# esp32_gps_pcb.net
KiCad netlist of a schematic drawn in EAGLE
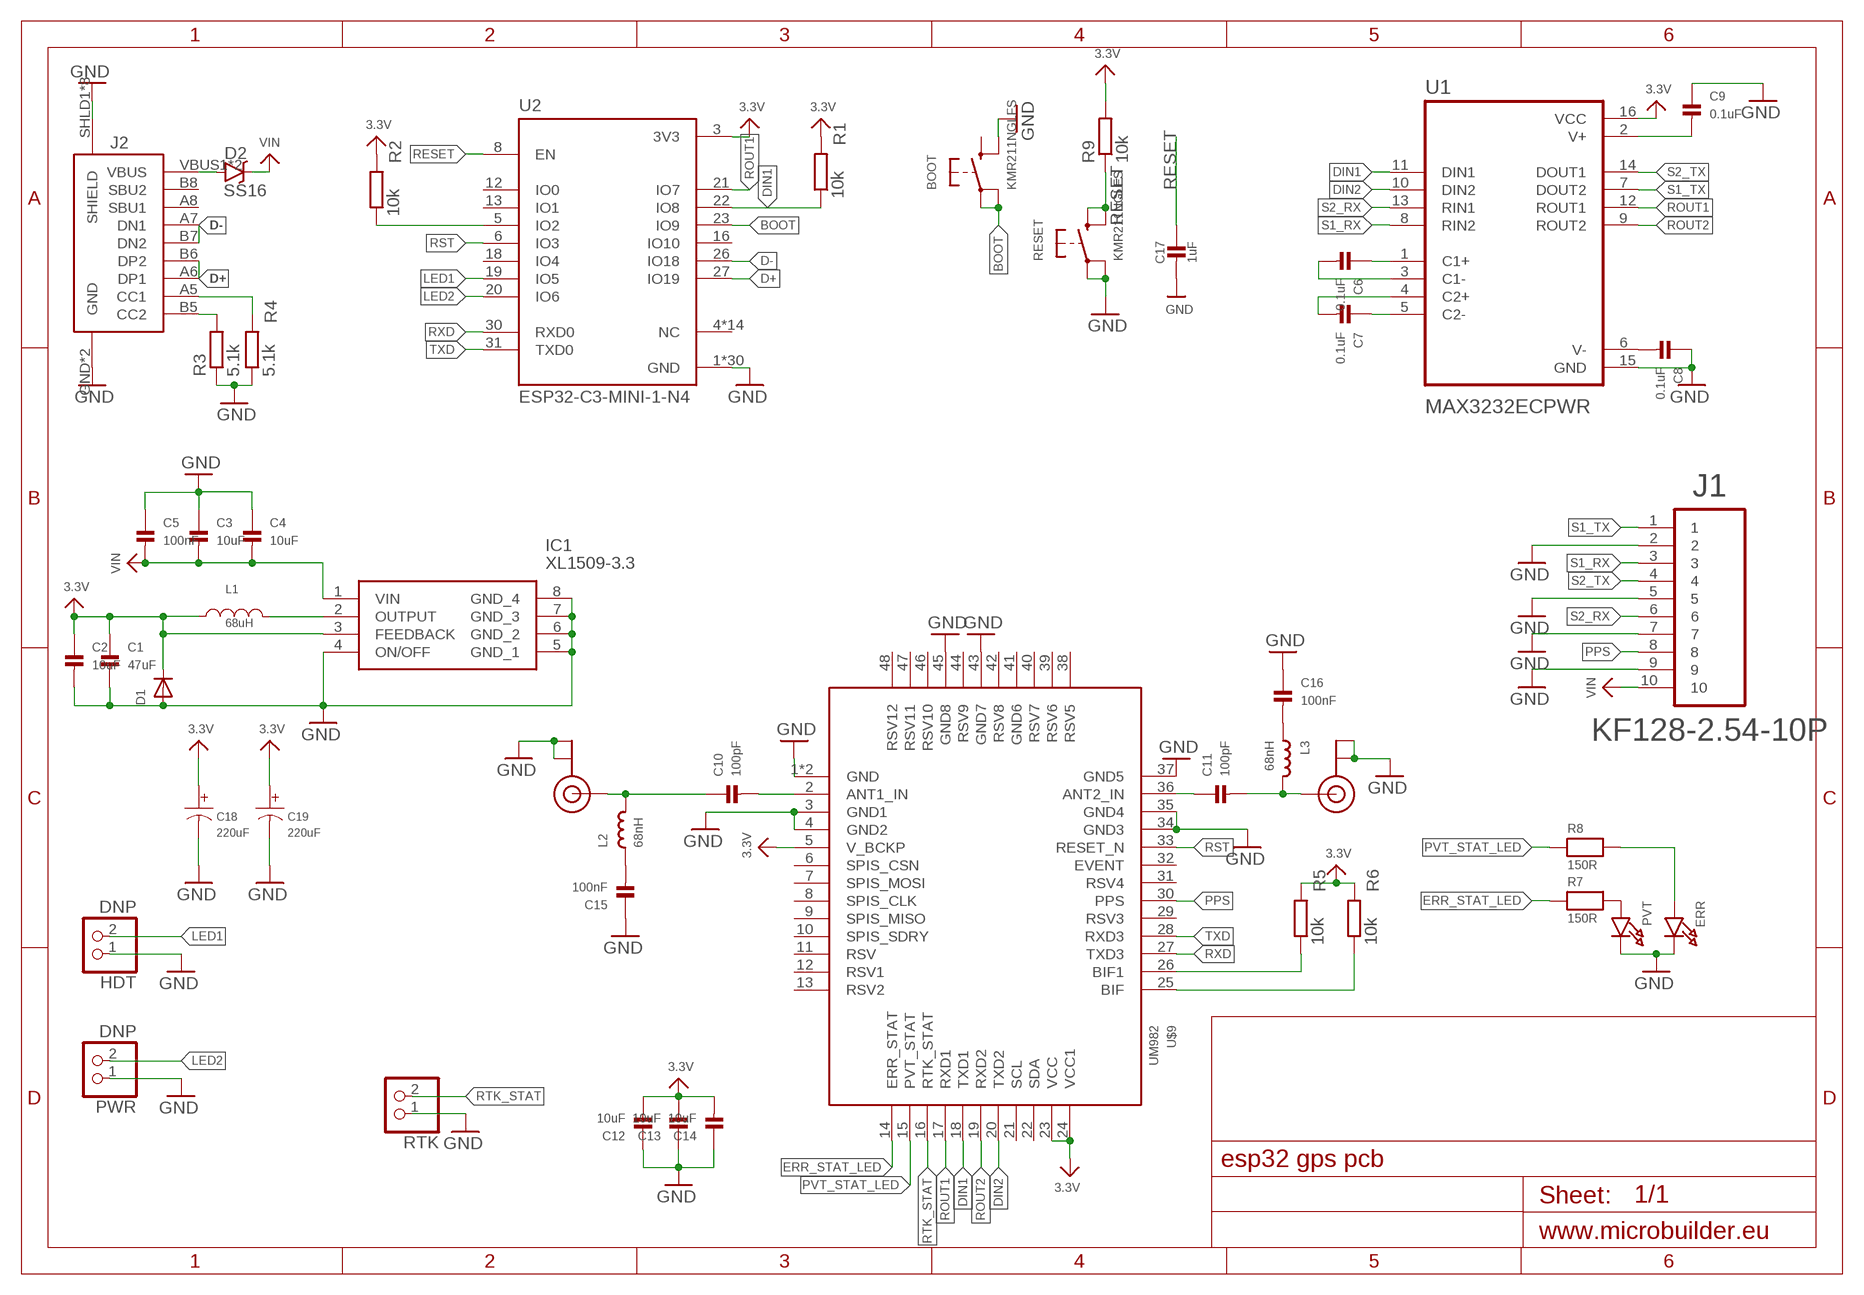
[diagram p0: schematic, sheet 1]

(export (version "E")
  (design (tool "Eeschema 10.0.6"))
  (components
    (comp (ref "BOOT")
      (value "KMR211NGLFS")
      (footprint "eagle-import:BTN_KMR2_4.6X2.8")
      (libsource (lib "eagle-import") (part "SWITCH_TACT_SMT4.6X2.8"))
    )
    (comp (ref "C1")
      (value "47uF")
      (footprint "eagle-import:_0805")
      (libsource (lib "eagle-import") (part "CAP_CERAMIC_0805"))
    )
    (comp (ref "C2")
      (value "10uF")
      (footprint "eagle-import:_0603")
      (libsource (lib "eagle-import") (part "CAP_CERAMIC_0603"))
    )
    (comp (ref "C3")
      (value "10uF")
      (footprint "eagle-import:_0603")
      (libsource (lib "eagle-import") (part "CAP_CERAMIC_0603"))
    )
    (comp (ref "C4")
      (value "10uF")
      (footprint "eagle-import:_0603")
      (libsource (lib "eagle-import") (part "CAP_CERAMIC_0603"))
    )
    (comp (ref "C5")
      (value "100nF")
      (footprint "eagle-import:_0603")
      (libsource (lib "eagle-import") (part "CAP_CERAMIC_0603"))
    )
    (comp (ref "C6")
      (value "0.1uF")
      (footprint "eagle-import:_0603")
      (libsource (lib "eagle-import") (part "CAP_CERAMIC_0603"))
    )
    (comp (ref "C7")
      (value "0.1uF")
      (footprint "eagle-import:_0603")
      (libsource (lib "eagle-import") (part "CAP_CERAMIC_0603"))
    )
    (comp (ref "C8")
      (value "0.1uF")
      (footprint "eagle-import:_0603")
      (libsource (lib "eagle-import") (part "CAP_CERAMIC_0603"))
    )
    (comp (ref "C9")
      (value "0.1uF")
      (footprint "eagle-import:_0603")
      (libsource (lib "eagle-import") (part "CAP_CERAMIC_0603"))
    )
    (comp (ref "C10")
      (value "100pF")
      (footprint "eagle-import:_0603")
      (fields (field (name "SPICEPREFIX") "C"))
      (libsource (lib "eagle-import") (part "CAP_CERAMIC_0603"))
    )
    (comp (ref "C11")
      (value "100pF")
      (footprint "eagle-import:_0603")
      (libsource (lib "eagle-import") (part "CAP_CERAMIC_0603"))
    )
    (comp (ref "C12")
      (value "10uF")
      (footprint "eagle-import:_0603")
      (libsource (lib "eagle-import") (part "CAP_CERAMIC_0603"))
    )
    (comp (ref "C13")
      (value "10uF")
      (footprint "eagle-import:_0603")
      (libsource (lib "eagle-import") (part "CAP_CERAMIC_0603"))
    )
    (comp (ref "C14")
      (value "10uF")
      (footprint "eagle-import:_0603")
      (libsource (lib "eagle-import") (part "CAP_CERAMIC_0603"))
    )
    (comp (ref "C15")
      (value "100nF")
      (footprint "eagle-import:_0603")
      (fields (field (name "SPICEPREFIX") "C"))
      (libsource (lib "eagle-import") (part "CAP_CERAMIC_0603"))
    )
    (comp (ref "C16")
      (value "100nF")
      (footprint "eagle-import:_0603")
      (fields (field (name "SPICEPREFIX") "C"))
      (libsource (lib "eagle-import") (part "CAP_CERAMIC_0603"))
    )
    (comp (ref "C17")
      (value "1uF")
      (footprint "eagle-import:_0603")
      (libsource (lib "eagle-import") (part "CAP_CERAMIC_0603"))
    )
    (comp (ref "C18")
      (value "220uF")
      (footprint "eagle-import:CAP-SMD_BD6.3-L6.6-W6.6-FD")
      (fields
        (field (name "BOM_MANUFACTURER_PART") "RVT1A221M0605")
        (field (name "BOM_SUPPLIER_PART") "C72494")
      )
      (libsource (lib "eagle-import") (part "220UF220UF_CAP-SMD_BD6.3-L6.6-W6.6-FD"))
    )
    (comp (ref "C19")
      (value "220uF")
      (footprint "eagle-import:CAP-SMD_BD6.3-L6.6-W6.6-FD")
      (fields
        (field (name "BOM_MANUFACTURER_PART") "RVT1A221M0605")
        (field (name "BOM_SUPPLIER_PART") "C72494")
      )
      (libsource (lib "eagle-import") (part "220UF220UF_CAP-SMD_BD6.3-L6.6-W6.6-FD"))
    )
    (comp (ref "D1")
      (value "DIODESMA")
      (footprint "eagle-import:SMADIODE")
      (libsource (lib "eagle-import") (part "DIODESMA"))
    )
    (comp (ref "D2")
      (value "SS16")
      (footprint "eagle-import:SMA-DIODE")
      (libsource (lib "eagle-import") (part "DIODE-SCHOTTKY-B340A"))
    )
    (comp (ref "ERR")
      (value "LED0603")
      (footprint "eagle-import:CHIPLED_0603")
      (libsource (lib "eagle-import") (part "LED0603"))
    )
    (comp (ref "HDT")
      (value "DNP")
      (footprint "eagle-import:1X02_ROUND")
      (libsource (lib "eagle-import") (part "HEADER-1X2ROUND"))
    )
    (comp (ref "IC1")
      (value "XL1509-3.3")
      (footprint "eagle-import:SOIC127P600X175-8N")
      (fields (field (name "MANUFACTURER_PART_NUMBER") " XL1509-3.3"))
      (libsource (lib "eagle-import") (part "XL1509-3.3"))
    )
    (comp (ref "J1")
      (value "KF128-2.54-10P")
      (footprint "eagle-import:KF128-2.54-10P")
      (fields
        (field (name "COMMENT") "1-282834-0")
        (field (name "DIGI-KEY_PART_NUMBER") "A98074-ND")
        (field (name "MF") "TE Connectivity")
      )
      (libsource (lib "eagle-import") (part "KF128-2.54-10P"))
    )
    (comp (ref "J2")
      (value "TYP-C16PIN2MD")
      (footprint "eagle-import:USB-C-16P")
      (libsource (lib "eagle-import") (part "TYP-C16PIN2MD"))
    )
    (comp (ref "L1")
      (value "68uH")
      (footprint "eagle-import:IND-SMD_L6.0-W6.0")
      (libsource (lib "eagle-import") (part "PNLS6045_680"))
    )
    (comp (ref "L2")
      (value "68nH")
      (footprint "eagle-import:_0603")
      (libsource (lib "eagle-import") (part "INDUCTOR_0603"))
    )
    (comp (ref "L3")
      (value "68nH")
      (footprint "eagle-import:_0603")
      (libsource (lib "eagle-import") (part "INDUCTOR_0603"))
    )
    (comp (ref "PRI")
      (value "KH-IPEX-K501-29")
      (footprint "eagle-import:U.FL")
      (libsource (lib "eagle-import") (part "U.FL"))
    )
    (comp (ref "PVT")
      (value "LED0603")
      (footprint "eagle-import:CHIPLED_0603")
      (libsource (lib "eagle-import") (part "LED0603"))
    )
    (comp (ref "PWR")
      (value "DNP")
      (footprint "eagle-import:1X02_ROUND")
      (libsource (lib "eagle-import") (part "HEADER-1X2ROUND"))
    )
    (comp (ref "R1")
      (value "10k")
      (footprint "eagle-import:R0402")
      (libsource (lib "eagle-import") (part "R-EU_R0402"))
    )
    (comp (ref "R2")
      (value "10k")
      (footprint "eagle-import:R0402")
      (libsource (lib "eagle-import") (part "R-EU_R0402"))
    )
    (comp (ref "R3")
      (value "5.1k")
      (footprint "eagle-import:R0402")
      (libsource (lib "eagle-import") (part "R-EU_R0402"))
    )
    (comp (ref "R4")
      (value "5.1k")
      (footprint "eagle-import:R0402")
      (libsource (lib "eagle-import") (part "R-EU_R0402"))
    )
    (comp (ref "R5")
      (value "10k")
      (footprint "eagle-import:R0402")
      (libsource (lib "eagle-import") (part "R-EU_R0402"))
    )
    (comp (ref "R6")
      (value "10k")
      (footprint "eagle-import:R0402")
      (libsource (lib "eagle-import") (part "R-EU_R0402"))
    )
    (comp (ref "R7")
      (value "150R")
      (footprint "eagle-import:_0603")
      (libsource (lib "eagle-import") (part "RESISTOR_0603"))
    )
    (comp (ref "R8")
      (value "150R")
      (footprint "eagle-import:_0603")
      (libsource (lib "eagle-import") (part "RESISTOR_0603"))
    )
    (comp (ref "R9")
      (value "10k")
      (footprint "eagle-import:R0603")
      (libsource (lib "eagle-import") (part "R-EU_R0603"))
    )
    (comp (ref "RESET")
      (value "KMR211NGLFS")
      (footprint "eagle-import:BTN_KMR2_4.6X2.8")
      (libsource (lib "eagle-import") (part "SWITCH_TACT_SMT4.6X2.8"))
    )
    (comp (ref "RTK")
      (value "HEADER-1X2ROUND")
      (footprint "eagle-import:1X02_ROUND")
      (libsource (lib "eagle-import") (part "HEADER-1X2ROUND"))
    )
    (comp (ref "SEC")
      (value "KH-IPEX-K501-29")
      (footprint "eagle-import:U.FL")
      (libsource (lib "eagle-import") (part "U.FL"))
    )
    (comp (ref "U$9")
      (value "UM982")
      (footprint "eagle-import:UM982")
      (libsource (lib "eagle-import") (part "UM982"))
    )
    (comp (ref "U1")
      (value "MAX3232ECPWR")
      (footprint "eagle-import:SOP65P640X120-16N")
      (libsource (lib "eagle-import") (part "MAX3232ECPWR"))
    )
    (comp (ref "U2")
      (value "ESP32-C3-MINI-1-N4")
      (footprint "eagle-import:XCVR_ESP32-C3-MINI-1-N4")
      (fields (field (name "MF") "Espressif Systems"))
      (libsource (lib "eagle-import") (part "ESP32-C3-MINI-1-N4"))
    )
  )
  (nets
    (net (code "1") (name "3.3V") (class "Default")
      (node (ref "C1") (pin "1") (pinfunction "P$1_1") (pintype "passive"))
      (node (ref "C12") (pin "2") (pinfunction "P$2_2") (pintype "passive"))
      (node (ref "C13") (pin "2") (pinfunction "P$2_2") (pintype "passive"))
      (node (ref "C14") (pin "2") (pinfunction "P$2_2") (pintype "passive"))
      (node (ref "C18") (pin "1") (pinfunction "1_1") (pintype "passive"))
      (node (ref "C19") (pin "1") (pinfunction "1_1") (pintype "passive"))
      (node (ref "C2") (pin "1") (pinfunction "P$1_1") (pintype "passive"))
      (node (ref "D1") (pin "C") (pinfunction "C_C") (pintype "passive"))
      (node (ref "IC1") (pin "3") (pinfunction "FEEDBACK_3") (pintype "bidirectional"))
      (node (ref "L1") (pin "1") (pinfunction "1_1") (pintype "passive"))
      (node (ref "R1") (pin "2") (pinfunction "2_2") (pintype "passive"))
      (node (ref "R2") (pin "2") (pinfunction "2_2") (pintype "passive"))
      (node (ref "R5") (pin "2") (pinfunction "2_2") (pintype "passive"))
      (node (ref "R6") (pin "2") (pinfunction "2_2") (pintype "passive"))
      (node (ref "R9") (pin "2") (pinfunction "2_2") (pintype "passive"))
      (node (ref "U$9") (pin "23") (pinfunction "VCC_23") (pintype "bidirectional"))
      (node (ref "U$9") (pin "24") (pinfunction "VCC1_24") (pintype "bidirectional"))
      (node (ref "U$9") (pin "5") (pinfunction "V_BCKP_5") (pintype "bidirectional"))
      (node (ref "U1") (pin "16") (pinfunction "VCC_16") (pintype "power_in"))
      (node (ref "U2") (pin "3") (pinfunction "3V3_3") (pintype "power_in"))
    )
    (net (code "2") (name "BOOT") (class "Default")
      (node (ref "BOOT") (pin "A") (pinfunction "P_A") (pintype "passive"))
      (node (ref "BOOT") (pin "A'") (pinfunction "P1_A'") (pintype "passive"))
      (node (ref "U2") (pin "23") (pinfunction "IO9_23") (pintype "bidirectional"))
    )
    (net (code "3") (name "D+") (class "Default")
      (node (ref "J2") (pin "A6") (pinfunction "DP1_A6") (pintype "bidirectional"))
      (node (ref "J2") (pin "B6") (pinfunction "DP2_B6") (pintype "bidirectional"))
      (node (ref "U2") (pin "27") (pinfunction "IO19_27") (pintype "bidirectional"))
    )
    (net (code "4") (name "D-") (class "Default")
      (node (ref "J2") (pin "A7") (pinfunction "DN1_A7") (pintype "bidirectional"))
      (node (ref "J2") (pin "B7") (pinfunction "DN2_B7") (pintype "bidirectional"))
      (node (ref "U2") (pin "26") (pinfunction "IO18_26") (pintype "bidirectional"))
    )
    (net (code "5") (name "DIN1") (class "Default")
      (node (ref "R1") (pin "1") (pinfunction "1_1") (pintype "passive"))
      (node (ref "U$9") (pin "18") (pinfunction "TXD1_18") (pintype "bidirectional"))
      (node (ref "U1") (pin "11") (pinfunction "DIN1_11") (pintype "input"))
      (node (ref "U2") (pin "22") (pinfunction "IO8_22") (pintype "bidirectional"))
    )
    (net (code "6") (name "DIN2") (class "Default")
      (node (ref "U$9") (pin "20") (pinfunction "TXD2_20") (pintype "bidirectional"))
      (node (ref "U1") (pin "10") (pinfunction "DIN2_10") (pintype "input"))
    )
    (net (code "7") (name "ERR_STAT_LED") (class "Default")
      (node (ref "R7") (pin "1") (pinfunction "1_1") (pintype "passive"))
      (node (ref "U$9") (pin "14") (pinfunction "ERR_STAT_14") (pintype "bidirectional"))
    )
    (net (code "8") (name "GND") (class "Default")
      (node (ref "BOOT") (pin "B'") (pinfunction "S1_B'") (pintype "passive"))
      (node (ref "C1") (pin "2") (pinfunction "P$2_2") (pintype "passive"))
      (node (ref "C12") (pin "1") (pinfunction "P$1_1") (pintype "passive"))
      (node (ref "C13") (pin "1") (pinfunction "P$1_1") (pintype "passive"))
      (node (ref "C14") (pin "1") (pinfunction "P$1_1") (pintype "passive"))
      (node (ref "C15") (pin "1") (pinfunction "P$1_1") (pintype "passive"))
      (node (ref "C16") (pin "1") (pinfunction "P$1_1") (pintype "passive"))
      (node (ref "C17") (pin "2") (pinfunction "P$2_2") (pintype "passive"))
      (node (ref "C18") (pin "2") (pinfunction "2_2") (pintype "passive"))
      (node (ref "C19") (pin "2") (pinfunction "2_2") (pintype "passive"))
      (node (ref "C2") (pin "2") (pinfunction "P$2_2") (pintype "passive"))
      (node (ref "C3") (pin "1") (pinfunction "P$1_1") (pintype "passive"))
      (node (ref "C4") (pin "1") (pinfunction "P$1_1") (pintype "passive"))
      (node (ref "C5") (pin "1") (pinfunction "P$1_1") (pintype "passive"))
      (node (ref "C8") (pin "1") (pinfunction "P$1_1") (pintype "passive"))
      (node (ref "C9") (pin "1") (pinfunction "P$1_1") (pintype "passive"))
      (node (ref "D1") (pin "A") (pinfunction "A_A") (pintype "passive"))
      (node (ref "ERR") (pin "C") (pinfunction "C_C") (pintype "passive"))
      (node (ref "HDT") (pin "1") (pinfunction "1_1") (pintype "passive"))
      (node (ref "IC1") (pin "4") (pinfunction "ON/OFF_4") (pintype "bidirectional"))
      (node (ref "IC1") (pin "5") (pinfunction "GND_1_5") (pintype "bidirectional"))
      (node (ref "IC1") (pin "6") (pinfunction "GND_2_6") (pintype "bidirectional"))
      (node (ref "IC1") (pin "7") (pinfunction "GND_3_7") (pintype "bidirectional"))
      (node (ref "IC1") (pin "8") (pinfunction "GND_4_8") (pintype "bidirectional"))
      (node (ref "J1") (pin "2") (pinfunction "2_2") (pintype "passive"))
      (node (ref "J1") (pin "5") (pinfunction "5_5") (pintype "passive"))
      (node (ref "J1") (pin "7") (pinfunction "7_7") (pintype "passive"))
      (node (ref "J1") (pin "9") (pinfunction "9_9") (pintype "passive"))
      (node (ref "J2") (pin "GND") (pinfunction "GND_GND") (pintype "power_in"))
      (node (ref "J2") (pin "GND2") (pinfunction "GND_GND2") (pintype "power_in"))
      (node (ref "J2") (pin "SHLD1") (pinfunction "SHIELD_SHLD1") (pintype "passive"))
      (node (ref "J2") (pin "SHLD2") (pinfunction "SHIELD_SHLD2") (pintype "passive"))
      (node (ref "J2") (pin "SHLD3") (pinfunction "SHIELD_SHLD3") (pintype "passive"))
      (node (ref "J2") (pin "SHLD4") (pinfunction "SHIELD_SHLD4") (pintype "passive"))
      (node (ref "J2") (pin "SHLD5") (pinfunction "SHIELD_SHLD5") (pintype "passive"))
      (node (ref "J2") (pin "SHLD6") (pinfunction "SHIELD_SHLD6") (pintype "passive"))
      (node (ref "J2") (pin "SHLD7") (pinfunction "SHIELD_SHLD7") (pintype "passive"))
      (node (ref "J2") (pin "SHLD8") (pinfunction "SHIELD_SHLD8") (pintype "passive"))
      (node (ref "PRI") (pin "1") (pinfunction "GND_1") (pintype "passive"))
      (node (ref "PRI") (pin "2") (pinfunction "GND_2") (pintype "passive"))
      (node (ref "PVT") (pin "C") (pinfunction "C_C") (pintype "passive"))
      (node (ref "PWR") (pin "1") (pinfunction "1_1") (pintype "passive"))
      (node (ref "R3") (pin "1") (pinfunction "1_1") (pintype "passive"))
      (node (ref "R4") (pin "1") (pinfunction "1_1") (pintype "passive"))
      (node (ref "RESET") (pin "A") (pinfunction "P_A") (pintype "passive"))
      (node (ref "RESET") (pin "A'") (pinfunction "P1_A'") (pintype "passive"))
      (node (ref "RTK") (pin "1") (pinfunction "1_1") (pintype "passive"))
      (node (ref "SEC") (pin "1") (pinfunction "GND_1") (pintype "passive"))
      (node (ref "SEC") (pin "2") (pinfunction "GND_2") (pintype "passive"))
      (node (ref "U$9") (pin "1") (pinfunction "GND_1") (pintype "bidirectional"))
      (node (ref "U$9") (pin "3") (pinfunction "GND1_3") (pintype "bidirectional"))
      (node (ref "U$9") (pin "34") (pinfunction "GND3_34") (pintype "bidirectional"))
      (node (ref "U$9") (pin "35") (pinfunction "GND4_35") (pintype "bidirectional"))
      (node (ref "U$9") (pin "37") (pinfunction "GND5_37") (pintype "bidirectional"))
      (node (ref "U$9") (pin "4") (pinfunction "GND2_4") (pintype "bidirectional"))
      (node (ref "U$9") (pin "43") (pinfunction "GND7_43") (pintype "bidirectional"))
      (node (ref "U$9") (pin "45") (pinfunction "GND8_45") (pintype "bidirectional"))
      (node (ref "U$9") (pin "P$1") (pinfunction "GND_P$1") (pintype "bidirectional"))
      (node (ref "U1") (pin "15") (pinfunction "GND_15") (pintype "power_in"))
      (node (ref "U2") (pin "1") (pinfunction "GND_1") (pintype "power_in"))
      (node (ref "U2") (pin "11") (pinfunction "GND_11") (pintype "power_in"))
      (node (ref "U2") (pin "14") (pinfunction "GND_14") (pintype "power_in"))
      (node (ref "U2") (pin "2") (pinfunction "GND_2") (pintype "power_in"))
      (node (ref "U2") (pin "36") (pinfunction "GND_36") (pintype "power_in"))
      (node (ref "U2") (pin "37") (pinfunction "GND_37") (pintype "power_in"))
      (node (ref "U2") (pin "38") (pinfunction "GND_38") (pintype "power_in"))
      (node (ref "U2") (pin "39") (pinfunction "GND_39") (pintype "power_in"))
      (node (ref "U2") (pin "40") (pinfunction "GND_40") (pintype "power_in"))
      (node (ref "U2") (pin "41") (pinfunction "GND_41") (pintype "power_in"))
      (node (ref "U2") (pin "42") (pinfunction "GND_42") (pintype "power_in"))
      (node (ref "U2") (pin "43") (pinfunction "GND_43") (pintype "power_in"))
      (node (ref "U2") (pin "44") (pinfunction "GND_44") (pintype "power_in"))
      (node (ref "U2") (pin "45") (pinfunction "GND_45") (pintype "power_in"))
      (node (ref "U2") (pin "46") (pinfunction "GND_46") (pintype "power_in"))
      (node (ref "U2") (pin "47") (pinfunction "GND_47") (pintype "power_in"))
      (node (ref "U2") (pin "48") (pinfunction "GND_48") (pintype "power_in"))
      (node (ref "U2") (pin "49_1") (pinfunction "GND_49_1") (pintype "power_in"))
      (node (ref "U2") (pin "49_2") (pinfunction "GND_49_2") (pintype "power_in"))
      (node (ref "U2") (pin "49_3") (pinfunction "GND_49_3") (pintype "power_in"))
      (node (ref "U2") (pin "49_4") (pinfunction "GND_49_4") (pintype "power_in"))
      (node (ref "U2") (pin "49_5") (pinfunction "GND_49_5") (pintype "power_in"))
      (node (ref "U2") (pin "49_6") (pinfunction "GND_49_6") (pintype "power_in"))
      (node (ref "U2") (pin "49_7") (pinfunction "GND_49_7") (pintype "power_in"))
      (node (ref "U2") (pin "49_8") (pinfunction "GND_49_8") (pintype "power_in"))
      (node (ref "U2") (pin "49_9") (pinfunction "GND_49_9") (pintype "power_in"))
      (node (ref "U2") (pin "50") (pinfunction "GND_50") (pintype "power_in"))
      (node (ref "U2") (pin "51") (pinfunction "GND_51") (pintype "power_in"))
      (node (ref "U2") (pin "52") (pinfunction "GND_52") (pintype "power_in"))
      (node (ref "U2") (pin "53") (pinfunction "GND_53") (pintype "power_in"))
    )
    (net (code "9") (name "LED1") (class "Default")
      (node (ref "HDT") (pin "2") (pinfunction "2_2") (pintype "passive"))
      (node (ref "U2") (pin "19") (pinfunction "IO5_19") (pintype "bidirectional"))
    )
    (net (code "10") (name "LED2") (class "Default")
      (node (ref "PWR") (pin "2") (pinfunction "2_2") (pintype "passive"))
      (node (ref "U2") (pin "20") (pinfunction "IO6_20") (pintype "bidirectional"))
    )
    (net (code "11") (name "Net-(C6-P$1)") (class "Default")
      (node (ref "C6") (pin "1") (pinfunction "P$1_1") (pintype "passive"))
      (node (ref "U1") (pin "1") (pinfunction "C1+_1") (pintype "bidirectional"))
    )
    (net (code "12") (name "Net-(C6-P$2)") (class "Default")
      (node (ref "C6") (pin "2") (pinfunction "P$2_2") (pintype "passive"))
      (node (ref "U1") (pin "3") (pinfunction "C1-_3") (pintype "bidirectional"))
    )
    (net (code "13") (name "Net-(C7-P$1)") (class "Default")
      (node (ref "C7") (pin "1") (pinfunction "P$1_1") (pintype "passive"))
      (node (ref "U1") (pin "5") (pinfunction "C2-_5") (pintype "bidirectional"))
    )
    (net (code "14") (name "Net-(C7-P$2)") (class "Default")
      (node (ref "C7") (pin "2") (pinfunction "P$2_2") (pintype "passive"))
      (node (ref "U1") (pin "4") (pinfunction "C2+_4") (pintype "bidirectional"))
    )
    (net (code "15") (name "Net-(C8-P$2)") (class "Default")
      (node (ref "C8") (pin "2") (pinfunction "P$2_2") (pintype "passive"))
      (node (ref "U1") (pin "6") (pinfunction "V-_6") (pintype "power_in"))
    )
    (net (code "16") (name "Net-(C9-P$2)") (class "Default")
      (node (ref "C9") (pin "2") (pinfunction "P$2_2") (pintype "passive"))
      (node (ref "U1") (pin "2") (pinfunction "V+_2") (pintype "power_in"))
    )
    (net (code "17") (name "Net-(C10-P$1)") (class "Default")
      (node (ref "C10") (pin "1") (pinfunction "P$1_1") (pintype "passive"))
      (node (ref "L2") (pin "2") (pinfunction "2_2") (pintype "passive"))
      (node (ref "PRI") (pin "3") (pinfunction "SIGNAL_3") (pintype "passive"))
    )
    (net (code "18") (name "Net-(C10-P$2)") (class "Default")
      (node (ref "C10") (pin "2") (pinfunction "P$2_2") (pintype "passive"))
      (node (ref "U$9") (pin "2") (pinfunction "ANT1_IN_2") (pintype "bidirectional"))
    )
    (net (code "19") (name "Net-(C11-P$1)") (class "Default")
      (node (ref "C11") (pin "1") (pinfunction "P$1_1") (pintype "passive"))
      (node (ref "U$9") (pin "36") (pinfunction "ANT2_IN_36") (pintype "bidirectional"))
    )
    (net (code "20") (name "Net-(C11-P$2)") (class "Default")
      (node (ref "C11") (pin "2") (pinfunction "P$2_2") (pintype "passive"))
      (node (ref "L3") (pin "2") (pinfunction "2_2") (pintype "passive"))
      (node (ref "SEC") (pin "3") (pinfunction "SIGNAL_3") (pintype "passive"))
    )
    (net (code "21") (name "Net-(C15-P$2)") (class "Default")
      (node (ref "C15") (pin "2") (pinfunction "P$2_2") (pintype "passive"))
      (node (ref "L2") (pin "1") (pinfunction "1_1") (pintype "passive"))
    )
    (net (code "22") (name "Net-(C16-P$2)") (class "Default")
      (node (ref "C16") (pin "2") (pinfunction "P$2_2") (pintype "passive"))
      (node (ref "L3") (pin "1") (pinfunction "1_1") (pintype "passive"))
    )
    (net (code "23") (name "Net-(D2-PadA)") (class "Default")
      (node (ref "D2") (pin "A") (pinfunction "A_A") (pintype "passive"))
      (node (ref "J2") (pin "VBUS1") (pinfunction "VBUS_VBUS1") (pintype "power_in"))
      (node (ref "J2") (pin "VBUS2") (pinfunction "VBUS_VBUS2") (pintype "power_in"))
    )
    (net (code "24") (name "Net-(ERR-PadA)") (class "Default")
      (node (ref "ERR") (pin "A") (pinfunction "A_A") (pintype "passive"))
      (node (ref "R8") (pin "2") (pinfunction "2_2") (pintype "passive"))
    )
    (net (code "25") (name "Net-(IC1-OUTPUT)") (class "Default")
      (node (ref "IC1") (pin "2") (pinfunction "OUTPUT_2") (pintype "bidirectional"))
      (node (ref "L1") (pin "2") (pinfunction "2_2") (pintype "passive"))
    )
    (net (code "26") (name "Net-(J2-CC1)") (class "Default")
      (node (ref "J2") (pin "A5") (pinfunction "CC1_A5") (pintype "bidirectional"))
      (node (ref "R4") (pin "2") (pinfunction "2_2") (pintype "passive"))
    )
    (net (code "27") (name "Net-(J2-CC2)") (class "Default")
      (node (ref "J2") (pin "B5") (pinfunction "CC2_B5") (pintype "bidirectional"))
      (node (ref "R3") (pin "2") (pinfunction "2_2") (pintype "passive"))
    )
    (net (code "28") (name "Net-(PVT-PadA)") (class "Default")
      (node (ref "PVT") (pin "A") (pinfunction "A_A") (pintype "passive"))
      (node (ref "R7") (pin "2") (pinfunction "2_2") (pintype "passive"))
    )
    (net (code "29") (name "Net-(U$9-BIF)") (class "Default")
      (node (ref "R6") (pin "1") (pinfunction "1_1") (pintype "passive"))
      (node (ref "U$9") (pin "25") (pinfunction "BIF_25") (pintype "bidirectional"))
    )
    (net (code "30") (name "Net-(U$9-BIF1)") (class "Default")
      (node (ref "R5") (pin "1") (pinfunction "1_1") (pintype "passive"))
      (node (ref "U$9") (pin "26") (pinfunction "BIF1_26") (pintype "bidirectional"))
    )
    (net (code "31") (name "Net-(U2-IO2)") (class "Default")
      (node (ref "R2") (pin "1") (pinfunction "1_1") (pintype "passive"))
      (node (ref "U2") (pin "5") (pinfunction "IO2_5") (pintype "bidirectional"))
    )
    (net (code "32") (name "PPS") (class "Default")
      (node (ref "J1") (pin "8") (pinfunction "8_8") (pintype "passive"))
      (node (ref "U$9") (pin "30") (pinfunction "PPS_30") (pintype "bidirectional"))
    )
    (net (code "33") (name "PVT_STAT_LED") (class "Default")
      (node (ref "R8") (pin "1") (pinfunction "1_1") (pintype "passive"))
      (node (ref "U$9") (pin "15") (pinfunction "PVT_STAT_15") (pintype "bidirectional"))
    )
    (net (code "34") (name "RESET") (class "Default")
      (node (ref "C17") (pin "1") (pinfunction "P$1_1") (pintype "passive"))
      (node (ref "R9") (pin "1") (pinfunction "1_1") (pintype "passive"))
      (node (ref "RESET") (pin "B") (pinfunction "S_B") (pintype "passive"))
      (node (ref "RESET") (pin "B'") (pinfunction "S1_B'") (pintype "passive"))
      (node (ref "U2") (pin "8") (pinfunction "EN_8") (pintype "input"))
    )
    (net (code "35") (name "ROUT1") (class "Default")
      (node (ref "U$9") (pin "17") (pinfunction "RXD1_17") (pintype "bidirectional"))
      (node (ref "U1") (pin "12") (pinfunction "ROUT1_12") (pintype "output"))
      (node (ref "U2") (pin "21") (pinfunction "IO7_21") (pintype "bidirectional"))
    )
    (net (code "36") (name "ROUT2") (class "Default")
      (node (ref "U$9") (pin "19") (pinfunction "RXD2_19") (pintype "bidirectional"))
      (node (ref "U1") (pin "9") (pinfunction "ROUT2_9") (pintype "output"))
    )
    (net (code "37") (name "RST") (class "Default")
      (node (ref "U$9") (pin "33") (pinfunction "RESET_N_33") (pintype "bidirectional"))
      (node (ref "U2") (pin "6") (pinfunction "IO3_6") (pintype "bidirectional"))
    )
    (net (code "38") (name "RTK_STAT") (class "Default")
      (node (ref "RTK") (pin "2") (pinfunction "2_2") (pintype "passive"))
      (node (ref "U$9") (pin "16") (pinfunction "RTK_STAT_16") (pintype "bidirectional"))
    )
    (net (code "39") (name "RXD") (class "Default")
      (node (ref "U$9") (pin "27") (pinfunction "TXD3_27") (pintype "bidirectional"))
      (node (ref "U2") (pin "30") (pinfunction "RXD0_30") (pintype "bidirectional"))
    )
    (net (code "40") (name "S1_RX") (class "Default")
      (node (ref "J1") (pin "3") (pinfunction "3_3") (pintype "passive"))
      (node (ref "U1") (pin "8") (pinfunction "RIN2_8") (pintype "input"))
    )
    (net (code "41") (name "S1_TX") (class "Default")
      (node (ref "J1") (pin "1") (pinfunction "1_1") (pintype "passive"))
      (node (ref "U1") (pin "7") (pinfunction "DOUT2_7") (pintype "output"))
    )
    (net (code "42") (name "S2_RX") (class "Default")
      (node (ref "J1") (pin "6") (pinfunction "6_6") (pintype "passive"))
      (node (ref "U1") (pin "13") (pinfunction "RIN1_13") (pintype "input"))
    )
    (net (code "43") (name "S2_TX") (class "Default")
      (node (ref "J1") (pin "4") (pinfunction "4_4") (pintype "passive"))
      (node (ref "U1") (pin "14") (pinfunction "DOUT1_14") (pintype "output"))
    )
    (net (code "44") (name "TXD") (class "Default")
      (node (ref "U$9") (pin "28") (pinfunction "RXD3_28") (pintype "bidirectional"))
      (node (ref "U2") (pin "31") (pinfunction "TXD0_31") (pintype "bidirectional"))
    )
    (net (code "45") (name "VIN") (class "Default")
      (node (ref "C3") (pin "2") (pinfunction "P$2_2") (pintype "passive"))
      (node (ref "C4") (pin "2") (pinfunction "P$2_2") (pintype "passive"))
      (node (ref "C5") (pin "2") (pinfunction "P$2_2") (pintype "passive"))
      (node (ref "D2") (pin "C") (pinfunction "C_C") (pintype "passive"))
      (node (ref "IC1") (pin "1") (pinfunction "VIN_1") (pintype "bidirectional"))
      (node (ref "J1") (pin "10") (pinfunction "10_10") (pintype "passive"))
    )
    (net (code "46") (name "unconnected-(BOOT-S-PadB)") (class "Default")
      (node (ref "BOOT") (pin "B") (pinfunction "S_B") (pintype "passive"))
    )
    (net (code "47") (name "unconnected-(J2-SBU1-PadA8)") (class "Default")
      (node (ref "J2") (pin "A8") (pinfunction "SBU1_A8") (pintype "bidirectional"))
    )
    (net (code "48") (name "unconnected-(J2-SBU2-PadB8)") (class "Default")
      (node (ref "J2") (pin "B8") (pinfunction "SBU2_B8") (pintype "bidirectional"))
    )
    (net (code "49") (name "unconnected-(U$9-EVENT-Pad32)") (class "Default")
      (node (ref "U$9") (pin "32") (pinfunction "EVENT_32") (pintype "bidirectional"))
    )
    (net (code "50") (name "unconnected-(U$9-GND6-Pad41)") (class "Default")
      (node (ref "U$9") (pin "41") (pinfunction "GND6_41") (pintype "bidirectional"))
    )
    (net (code "51") (name "unconnected-(U$9-RSV-Pad11)") (class "Default")
      (node (ref "U$9") (pin "11") (pinfunction "RSV_11") (pintype "bidirectional"))
    )
    (net (code "52") (name "unconnected-(U$9-RSV1-Pad12)") (class "Default")
      (node (ref "U$9") (pin "12") (pinfunction "RSV1_12") (pintype "bidirectional"))
    )
    (net (code "53") (name "unconnected-(U$9-RSV2-Pad13)") (class "Default")
      (node (ref "U$9") (pin "13") (pinfunction "RSV2_13") (pintype "bidirectional"))
    )
    (net (code "54") (name "unconnected-(U$9-RSV3-Pad29)") (class "Default")
      (node (ref "U$9") (pin "29") (pinfunction "RSV3_29") (pintype "bidirectional"))
    )
    (net (code "55") (name "unconnected-(U$9-RSV4-Pad31)") (class "Default")
      (node (ref "U$9") (pin "31") (pinfunction "RSV4_31") (pintype "bidirectional"))
    )
    (net (code "56") (name "unconnected-(U$9-RSV5-Pad38)") (class "Default")
      (node (ref "U$9") (pin "38") (pinfunction "RSV5_38") (pintype "bidirectional"))
    )
    (net (code "57") (name "unconnected-(U$9-RSV6-Pad39)") (class "Default")
      (node (ref "U$9") (pin "39") (pinfunction "RSV6_39") (pintype "bidirectional"))
    )
    (net (code "58") (name "unconnected-(U$9-RSV7-Pad40)") (class "Default")
      (node (ref "U$9") (pin "40") (pinfunction "RSV7_40") (pintype "bidirectional"))
    )
    (net (code "59") (name "unconnected-(U$9-RSV8-Pad42)") (class "Default")
      (node (ref "U$9") (pin "42") (pinfunction "RSV8_42") (pintype "bidirectional"))
    )
    (net (code "60") (name "unconnected-(U$9-RSV9-Pad44)") (class "Default")
      (node (ref "U$9") (pin "44") (pinfunction "RSV9_44") (pintype "bidirectional"))
    )
    (net (code "61") (name "unconnected-(U$9-RSV10-Pad46)") (class "Default")
      (node (ref "U$9") (pin "46") (pinfunction "RSV10_46") (pintype "bidirectional"))
    )
    (net (code "62") (name "unconnected-(U$9-RSV11-Pad47)") (class "Default")
      (node (ref "U$9") (pin "47") (pinfunction "RSV11_47") (pintype "bidirectional"))
    )
    (net (code "63") (name "unconnected-(U$9-RSV12-Pad48)") (class "Default")
      (node (ref "U$9") (pin "48") (pinfunction "RSV12_48") (pintype "bidirectional"))
    )
    (net (code "64") (name "unconnected-(U$9-SCL-Pad21)") (class "Default")
      (node (ref "U$9") (pin "21") (pinfunction "SCL_21") (pintype "bidirectional"))
    )
    (net (code "65") (name "unconnected-(U$9-SDA-Pad22)") (class "Default")
      (node (ref "U$9") (pin "22") (pinfunction "SDA_22") (pintype "bidirectional"))
    )
    (net (code "66") (name "unconnected-(U$9-SPIS_CLK-Pad8)") (class "Default")
      (node (ref "U$9") (pin "8") (pinfunction "SPIS_CLK_8") (pintype "bidirectional"))
    )
    (net (code "67") (name "unconnected-(U$9-SPIS_CSN-Pad6)") (class "Default")
      (node (ref "U$9") (pin "6") (pinfunction "SPIS_CSN_6") (pintype "bidirectional"))
    )
    (net (code "68") (name "unconnected-(U$9-SPIS_MISO-Pad9)") (class "Default")
      (node (ref "U$9") (pin "9") (pinfunction "SPIS_MISO_9") (pintype "bidirectional"))
    )
    (net (code "69") (name "unconnected-(U$9-SPIS_MOSI-Pad7)") (class "Default")
      (node (ref "U$9") (pin "7") (pinfunction "SPIS_MOSI_7") (pintype "bidirectional"))
    )
    (net (code "70") (name "unconnected-(U$9-SPIS_SDRY-Pad10)") (class "Default")
      (node (ref "U$9") (pin "10") (pinfunction "SPIS_SDRY_10") (pintype "bidirectional"))
    )
    (net (code "71") (name "unconnected-(U2-IO0-Pad12)") (class "Default")
      (node (ref "U2") (pin "12") (pinfunction "IO0_12") (pintype "bidirectional"))
    )
    (net (code "72") (name "unconnected-(U2-IO1-Pad13)") (class "Default")
      (node (ref "U2") (pin "13") (pinfunction "IO1_13") (pintype "bidirectional"))
    )
    (net (code "73") (name "unconnected-(U2-IO4-Pad18)") (class "Default")
      (node (ref "U2") (pin "18") (pinfunction "IO4_18") (pintype "bidirectional"))
    )
    (net (code "74") (name "unconnected-(U2-IO10-Pad16)") (class "Default")
      (node (ref "U2") (pin "16") (pinfunction "IO10_16") (pintype "bidirectional"))
    )
    (net (code "75") (name "unconnected-(U2-NC-Pad4)") (class "Default")
      (node (ref "U2") (pin "4") (pinfunction "NC_4") (pintype "no_connect"))
    )
    (net (code "76") (name "unconnected-(U2-NC-Pad7)") (class "Default")
      (node (ref "U2") (pin "7") (pinfunction "NC_7") (pintype "no_connect"))
    )
    (net (code "77") (name "unconnected-(U2-NC-Pad9)") (class "Default")
      (node (ref "U2") (pin "9") (pinfunction "NC_9") (pintype "no_connect"))
    )
    (net (code "78") (name "unconnected-(U2-NC-Pad10)") (class "Default")
      (node (ref "U2") (pin "10") (pinfunction "NC_10") (pintype "no_connect"))
    )
    (net (code "79") (name "unconnected-(U2-NC-Pad15)") (class "Default")
      (node (ref "U2") (pin "15") (pinfunction "NC_15") (pintype "no_connect"))
    )
    (net (code "80") (name "unconnected-(U2-NC-Pad17)") (class "Default")
      (node (ref "U2") (pin "17") (pinfunction "NC_17") (pintype "no_connect"))
    )
    (net (code "81") (name "unconnected-(U2-NC-Pad24)") (class "Default")
      (node (ref "U2") (pin "24") (pinfunction "NC_24") (pintype "no_connect"))
    )
    (net (code "82") (name "unconnected-(U2-NC-Pad25)") (class "Default")
      (node (ref "U2") (pin "25") (pinfunction "NC_25") (pintype "no_connect"))
    )
    (net (code "83") (name "unconnected-(U2-NC-Pad28)") (class "Default")
      (node (ref "U2") (pin "28") (pinfunction "NC_28") (pintype "no_connect"))
    )
    (net (code "84") (name "unconnected-(U2-NC-Pad29)") (class "Default")
      (node (ref "U2") (pin "29") (pinfunction "NC_29") (pintype "no_connect"))
    )
    (net (code "85") (name "unconnected-(U2-NC-Pad32)") (class "Default")
      (node (ref "U2") (pin "32") (pinfunction "NC_32") (pintype "no_connect"))
    )
    (net (code "86") (name "unconnected-(U2-NC-Pad33)") (class "Default")
      (node (ref "U2") (pin "33") (pinfunction "NC_33") (pintype "no_connect"))
    )
    (net (code "87") (name "unconnected-(U2-NC-Pad34)") (class "Default")
      (node (ref "U2") (pin "34") (pinfunction "NC_34") (pintype "no_connect"))
    )
    (net (code "88") (name "unconnected-(U2-NC-Pad35)") (class "Default")
      (node (ref "U2") (pin "35") (pinfunction "NC_35") (pintype "no_connect"))
    )
  )
)
